# schematic_tsc.net
KiCad netlist of a schematic drawn in EAGLE
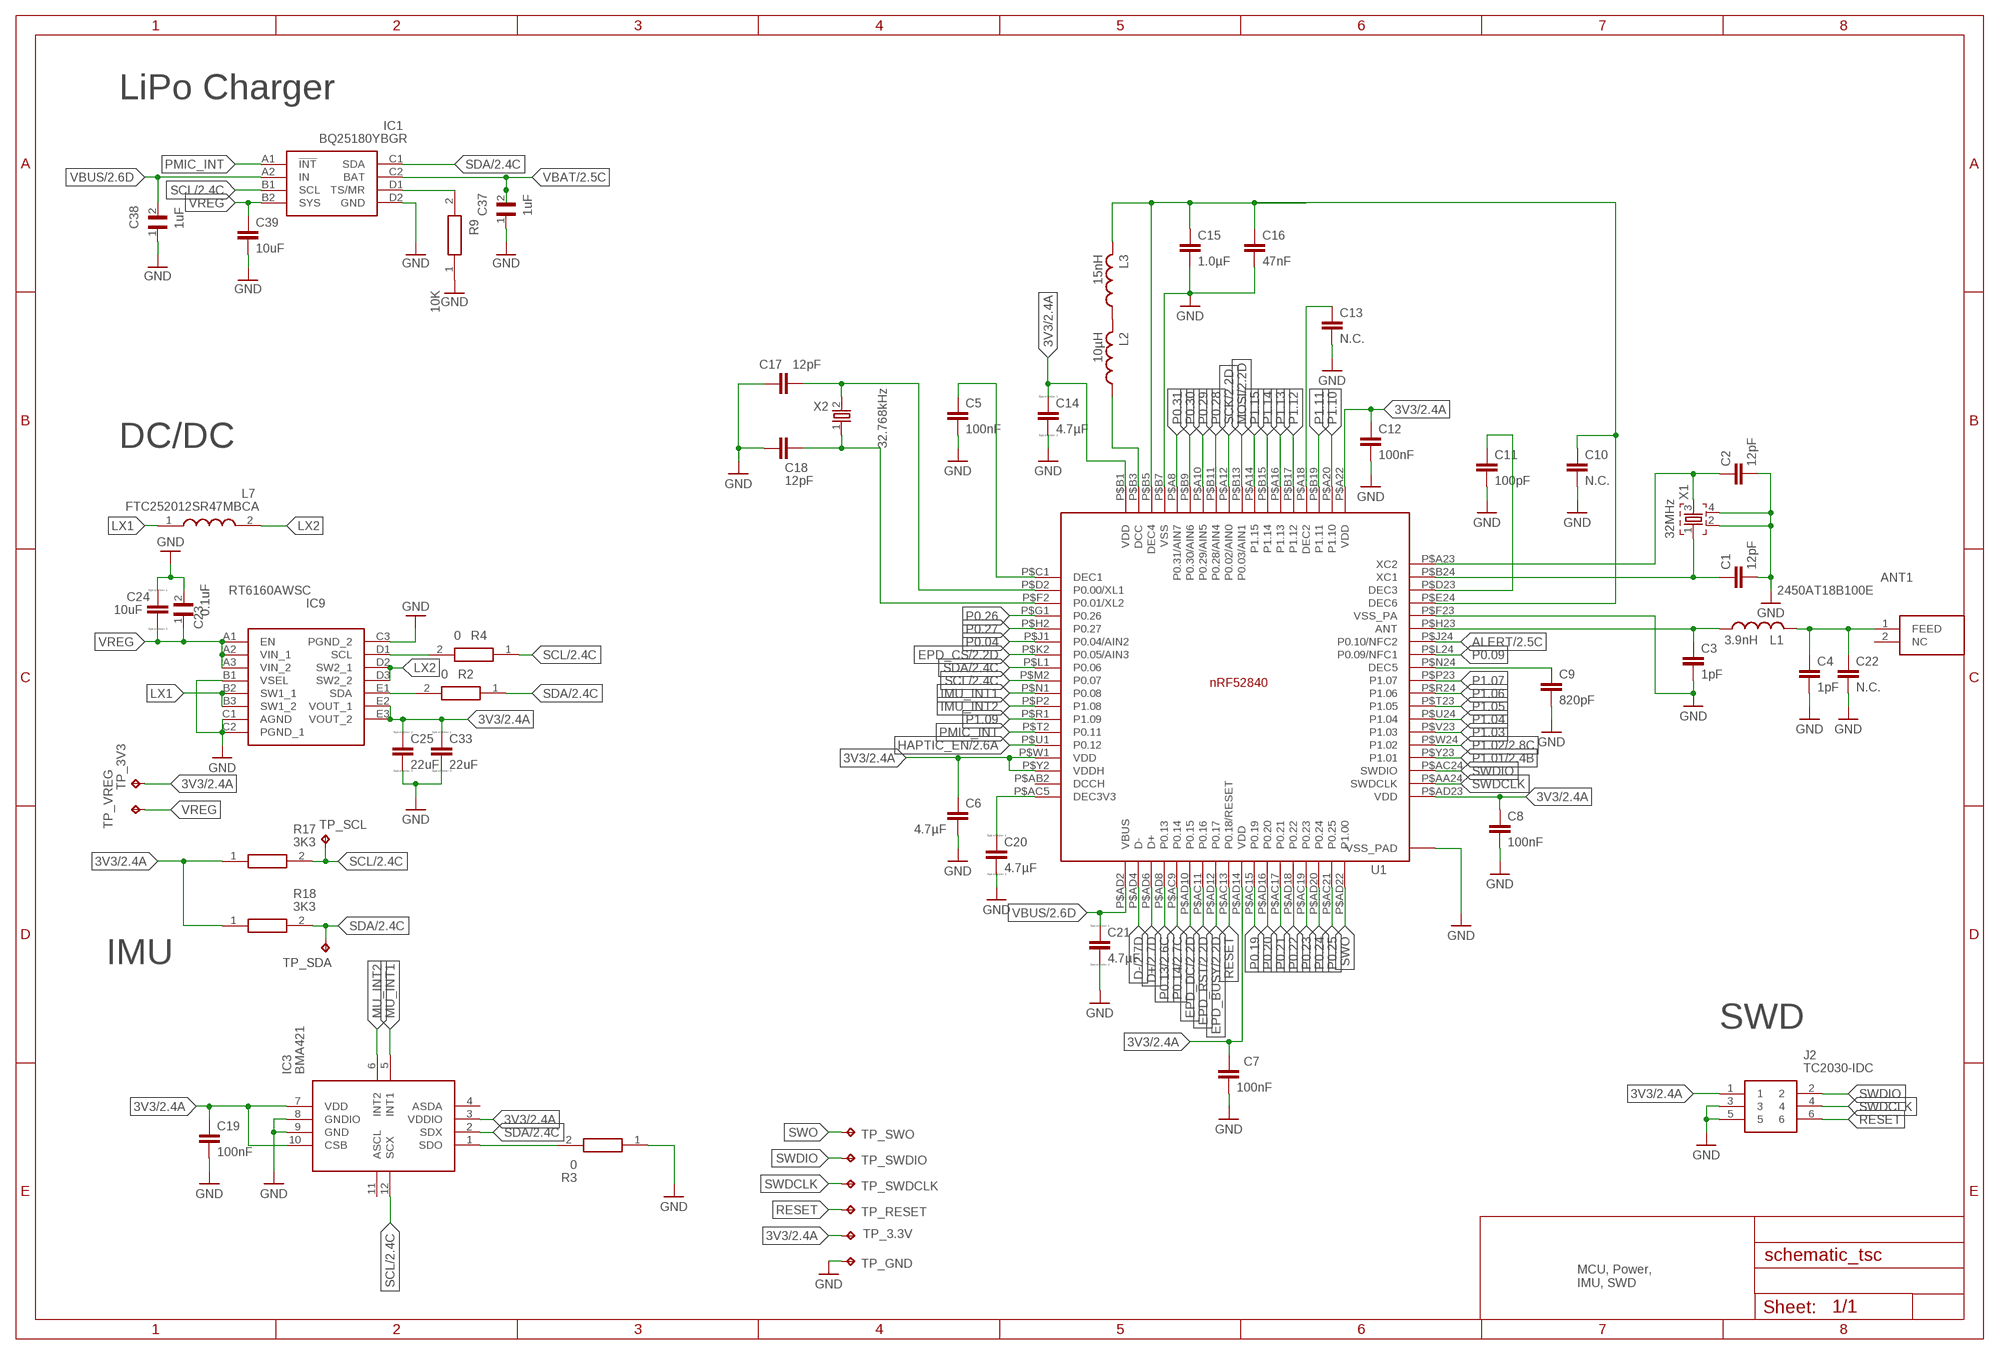
[diagram p0: schematic, sheet 1, part 1 of 2]
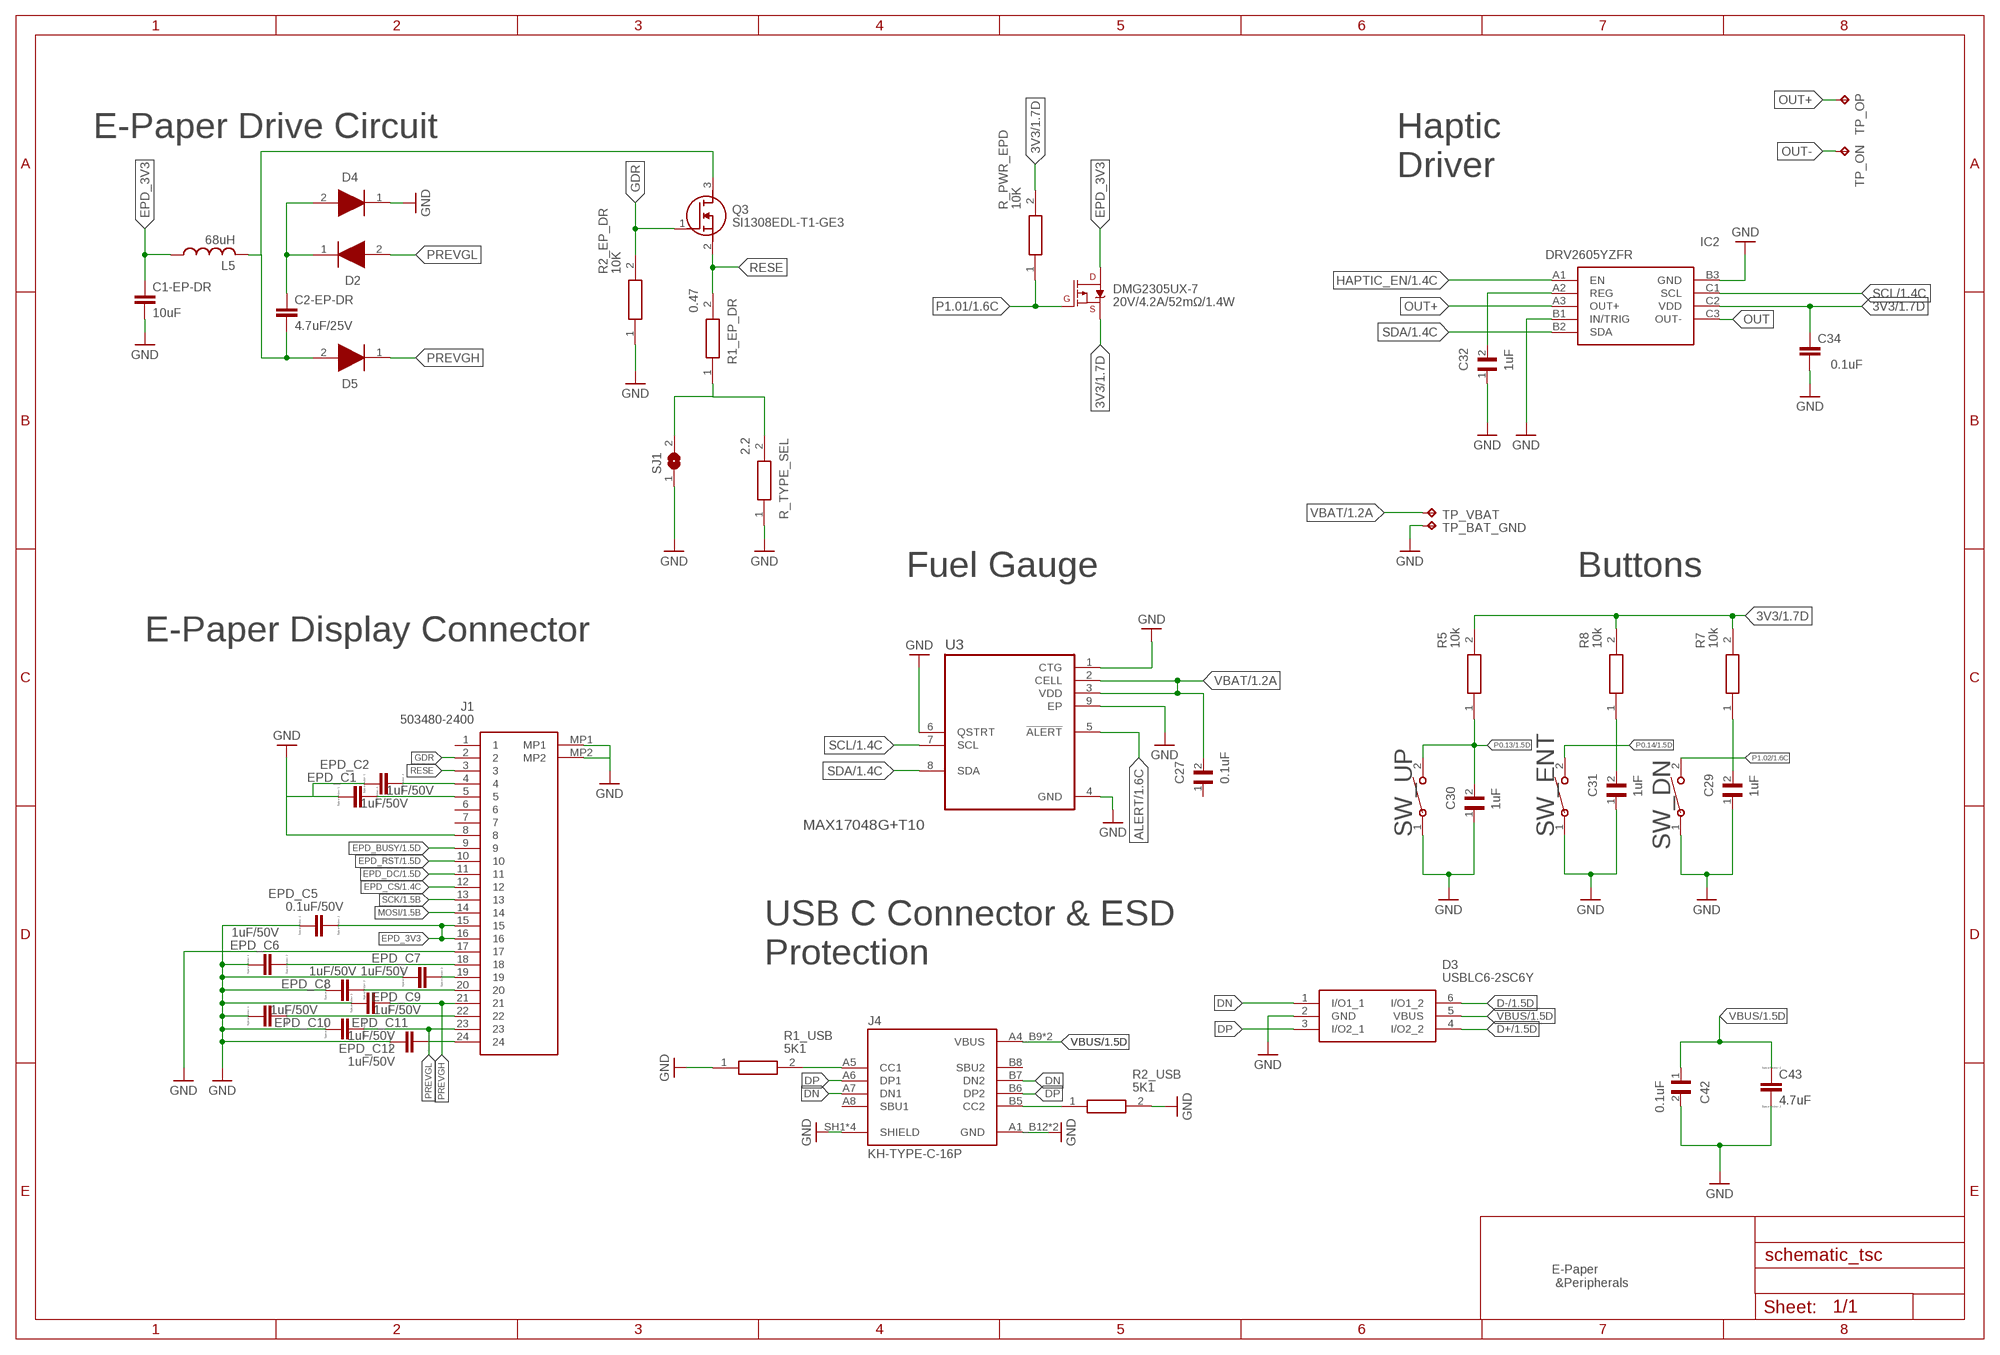
[diagram p1: schematic, sheet 1, part 2 of 2]

(export (version "E")
  (design (tool "Eeschema 10.0.6"))
  (components
    (comp (ref "ANT1")
      (value "2450AT18B100E")
      (footprint "eagle-import:2450AT18B100E_ANTC3216X140N")
      (fields (field (name "MOUSER_PART_NUMBER") "609-2450AT18B100E"))
      (libsource (lib "eagle-import") (part "2450AT18B100E_2450AT18B100E"))
    )
    (comp (ref "C1")
      (value "12pF")
      (footprint "eagle-import:NORDIC_NRF_3_RESC0201_L")
      (libsource (lib "eagle-import") (part "NORDIC_NRF_3_CAPACITOR_0201_L"))
    )
    (comp (ref "C1-EP-DR")
      (value "10uF")
      (footprint "eagle-import:NORDIC_NRF_3_RESC0201_L")
      (libsource (lib "eagle-import") (part "NORDIC_NRF_3_CAPACITOR_0201_L"))
    )
    (comp (ref "C2")
      (value "12pF")
      (footprint "eagle-import:NORDIC_NRF_3_RESC0201_L")
      (libsource (lib "eagle-import") (part "NORDIC_NRF_3_CAPACITOR_0201_L"))
    )
    (comp (ref "C2-EP-DR")
      (value "4.7uF/25V")
      (footprint "eagle-import:NORDIC_NRF_3_RESC0201_L")
      (libsource (lib "eagle-import") (part "NORDIC_NRF_3_CAPACITOR_0201_L"))
    )
    (comp (ref "C3")
      (value "1pF")
      (footprint "eagle-import:NORDIC_NRF_3_RESC0201_L")
      (libsource (lib "eagle-import") (part "NORDIC_NRF_3_CAPACITOR_0201_L"))
    )
    (comp (ref "C4")
      (value "1pF")
      (footprint "eagle-import:NORDIC_NRF_3_RESC0201_L")
      (libsource (lib "eagle-import") (part "NORDIC_NRF_3_CAPACITOR_0201_L"))
    )
    (comp (ref "C5")
      (value "100nF")
      (footprint "eagle-import:NORDIC_NRF_3_RESC0201_L")
      (libsource (lib "eagle-import") (part "NORDIC_NRF_3_CAPACITOR_0201_L"))
    )
    (comp (ref "C6")
      (value "4.7µF")
      (footprint "eagle-import:NORDIC_NRF_3_RESC0201_L")
      (libsource (lib "eagle-import") (part "NORDIC_NRF_3_CAPACITOR_0201_L"))
    )
    (comp (ref "C7")
      (value "100nF")
      (footprint "eagle-import:NORDIC_NRF_3_RESC0201_L")
      (libsource (lib "eagle-import") (part "NORDIC_NRF_3_CAPACITOR_0201_L"))
    )
    (comp (ref "C8")
      (value "100nF")
      (footprint "eagle-import:NORDIC_NRF_3_RESC0201_L")
      (libsource (lib "eagle-import") (part "NORDIC_NRF_3_CAPACITOR_0201_L"))
    )
    (comp (ref "C9")
      (value "820pF")
      (footprint "eagle-import:NORDIC_NRF_3_RESC0201_L")
      (libsource (lib "eagle-import") (part "NORDIC_NRF_3_CAPACITOR_0201_L"))
    )
    (comp (ref "C10")
      (value "N.C.")
      (footprint "eagle-import:NORDIC_NRF_3_RESC0201_L")
      (libsource (lib "eagle-import") (part "NORDIC_NRF_3_CAPACITOR_0201_L"))
    )
    (comp (ref "C11")
      (value "100pF")
      (footprint "eagle-import:NORDIC_NRF_3_RESC0201_L")
      (libsource (lib "eagle-import") (part "NORDIC_NRF_3_CAPACITOR_0201_L"))
    )
    (comp (ref "C12")
      (value "100nF")
      (footprint "eagle-import:NORDIC_NRF_3_RESC0201_L")
      (libsource (lib "eagle-import") (part "NORDIC_NRF_3_CAPACITOR_0201_L"))
    )
    (comp (ref "C13")
      (value "N.C.")
      (footprint "eagle-import:NORDIC_NRF_3_RESC0201_L")
      (libsource (lib "eagle-import") (part "NORDIC_NRF_3_CAPACITOR_0201_L"))
    )
    (comp (ref "C14")
      (value "4.7µF")
      (footprint "eagle-import:ESP32_C6_LIBRARY_1_ESP32_WROVER_EAGLE-LTSPICE_C0402")
      (libsource (lib "eagle-import") (part "ESP32_C6_LIBRARY_1_ESP32_WROVER_EAGLE-LTSPICE_CC0402"))
    )
    (comp (ref "C15")
      (value "1.0µF")
      (footprint "eagle-import:NORDIC_NRF_3_RESC0201_L")
      (libsource (lib "eagle-import") (part "NORDIC_NRF_3_CAPACITOR_0201_L"))
    )
    (comp (ref "C16")
      (value "47nF")
      (footprint "eagle-import:NORDIC_NRF_3_RESC0201_L")
      (libsource (lib "eagle-import") (part "NORDIC_NRF_3_CAPACITOR_0201_L"))
    )
    (comp (ref "C17")
      (value "12pF")
      (footprint "eagle-import:NORDIC_NRF_3_RESC0201_L")
      (libsource (lib "eagle-import") (part "NORDIC_NRF_3_CAPACITOR_0201_L"))
    )
    (comp (ref "C18")
      (value "12pF")
      (footprint "eagle-import:NORDIC_NRF_3_RESC0201_L")
      (libsource (lib "eagle-import") (part "NORDIC_NRF_3_CAPACITOR_0201_L"))
    )
    (comp (ref "C19")
      (value "100nF")
      (footprint "eagle-import:NORDIC_NRF_3_RESC0201_L")
      (libsource (lib "eagle-import") (part "NORDIC_NRF_3_CAPACITOR_0201_L"))
    )
    (comp (ref "C20")
      (value "4.7µF")
      (footprint "eagle-import:ESP32_C6_LIBRARY_1_ESP32_WROVER_EAGLE-LTSPICE_C0402")
      (libsource (lib "eagle-import") (part "ESP32_C6_LIBRARY_1_ESP32_WROVER_EAGLE-LTSPICE_CC0402"))
    )
    (comp (ref "C21")
      (value "4.7µF")
      (footprint "eagle-import:ESP32_C6_LIBRARY_1_ESP32_WROVER_EAGLE-LTSPICE_C0402")
      (libsource (lib "eagle-import") (part "ESP32_C6_LIBRARY_1_ESP32_WROVER_EAGLE-LTSPICE_CC0402"))
    )
    (comp (ref "C22")
      (value "N.C.")
      (footprint "eagle-import:NORDIC_NRF_3_RESC0201_L")
      (libsource (lib "eagle-import") (part "NORDIC_NRF_3_CAPACITOR_0201_L"))
    )
    (comp (ref "C23")
      (value "0.1uF")
      (footprint "eagle-import:GRM011R60J152KE01L_2_CAPC0201X13N")
      (fields (field (name "MF") "Murata") (field (name "MP") "GRM011R60J152KE01L"))
      (libsource (lib "eagle-import") (part "GRM011R60J152KE01L_2_GRM011R60J152KE01L"))
    )
    (comp (ref "C24")
      (value "10uF")
      (footprint "eagle-import:ESP32_C6_LIBRARY_1_ESP32_WROVER_EAGLE-LTSPICE_C0402")
      (libsource (lib "eagle-import") (part "ESP32_C6_LIBRARY_1_ESP32_WROVER_EAGLE-LTSPICE_CC0402"))
    )
    (comp (ref "C25")
      (value "22uF")
      (footprint "eagle-import:ESP32_C6_LIBRARY_1_ESP32_WROVER_EAGLE-LTSPICE_C0402")
      (libsource (lib "eagle-import") (part "ESP32_C6_LIBRARY_1_ESP32_WROVER_EAGLE-LTSPICE_CC0402"))
    )
    (comp (ref "C27")
      (value "0.1uF")
      (footprint "eagle-import:GRM011R60J152KE01L_2_CAPC0201X13N")
      (fields (field (name "MF") "Murata") (field (name "MP") "GRM011R60J152KE01L"))
      (libsource (lib "eagle-import") (part "GRM011R60J152KE01L_2_GRM011R60J152KE01L"))
    )
    (comp (ref "C29")
      (value "1uF")
      (footprint "eagle-import:GRM011R60J152KE01L_2_CAPC0201X13N")
      (fields (field (name "MF") "Murata") (field (name "MP") "GRM011R60J152KE01L"))
      (libsource (lib "eagle-import") (part "GRM011R60J152KE01L_2_GRM011R60J152KE01L"))
    )
    (comp (ref "C30")
      (value "1uF")
      (footprint "eagle-import:GRM011R60J152KE01L_2_CAPC0201X13N")
      (fields (field (name "MF") "Murata") (field (name "MP") "GRM011R60J152KE01L"))
      (libsource (lib "eagle-import") (part "GRM011R60J152KE01L_2_GRM011R60J152KE01L"))
    )
    (comp (ref "C31")
      (value "1uF")
      (footprint "eagle-import:GRM011R60J152KE01L_2_CAPC0201X13N")
      (fields (field (name "MF") "Murata") (field (name "MP") "GRM011R60J152KE01L"))
      (libsource (lib "eagle-import") (part "GRM011R60J152KE01L_2_GRM011R60J152KE01L"))
    )
    (comp (ref "C32")
      (value "1uF")
      (footprint "eagle-import:GRM011R60J152KE01L_2_CAPC0201X13N")
      (fields (field (name "MF") "Murata") (field (name "MP") "GRM011R60J152KE01L"))
      (libsource (lib "eagle-import") (part "GRM011R60J152KE01L_2_GRM011R60J152KE01L"))
    )
    (comp (ref "C33")
      (value "22uF")
      (footprint "eagle-import:ESP32_C6_LIBRARY_1_ESP32_WROVER_EAGLE-LTSPICE_C0402")
      (libsource (lib "eagle-import") (part "ESP32_C6_LIBRARY_1_ESP32_WROVER_EAGLE-LTSPICE_CC0402"))
    )
    (comp (ref "C34")
      (value "0.1uF")
      (footprint "eagle-import:NORDIC_NRF_3_RESC0201_L")
      (libsource (lib "eagle-import") (part "NORDIC_NRF_3_CAPACITOR_0201_L"))
    )
    (comp (ref "C37")
      (value "1uF")
      (footprint "eagle-import:GRM011R60J152KE01L_2_CAPC0201X13N")
      (fields (field (name "MF") "Murata") (field (name "MP") "GRM011R60J152KE01L"))
      (libsource (lib "eagle-import") (part "GRM011R60J152KE01L_2_GRM011R60J152KE01L"))
    )
    (comp (ref "C38")
      (value "1uF")
      (footprint "eagle-import:GRM011R60J152KE01L_2_CAPC0201X13N")
      (fields (field (name "MF") "Murata") (field (name "MP") "GRM011R60J152KE01L"))
      (libsource (lib "eagle-import") (part "GRM011R60J152KE01L_2_GRM011R60J152KE01L"))
    )
    (comp (ref "C39")
      (value "10uF")
      (footprint "eagle-import:NORDIC_NRF_3_RESC0201_L")
      (libsource (lib "eagle-import") (part "NORDIC_NRF_3_CAPACITOR_0201_L"))
    )
    (comp (ref "C42")
      (value "0.1uF")
      (footprint "eagle-import:GRM011R60J152KE01L_2_CAPC0201X13N")
      (fields (field (name "MF") "Murata") (field (name "MP") "GRM011R60J152KE01L"))
      (libsource (lib "eagle-import") (part "GRM011R60J152KE01L_2_GRM011R60J152KE01L"))
    )
    (comp (ref "C43")
      (value "4.7uF")
      (footprint "eagle-import:ESP32_C6_LIBRARY_1_ESP32_WROVER_EAGLE-LTSPICE_C0402")
      (libsource (lib "eagle-import") (part "ESP32_C6_LIBRARY_1_ESP32_WROVER_EAGLE-LTSPICE_CC0402"))
    )
    (comp (ref "D2")
      (value "ESP32_C6_LIBRARY_5_MBR0530")
      (footprint "eagle-import:ESP32_C6_LIBRARY_5_SOD3716X135N")
      (fields (field (name "MF") "ON Semiconductor") (field (name "MP") "MBR0530"))
      (libsource (lib "eagle-import") (part "ESP32_C6_LIBRARY_5_MBR0530"))
    )
    (comp (ref "D3")
      (value "USBLC6-2SC6Y")
      (footprint "eagle-import:ESP32_C6_LIBRARY_3_SOT95P280X145-6N")
      (fields (field (name "MF") "STMicroelectronics"))
      (libsource (lib "eagle-import") (part "ESP32_C6_LIBRARY_3_USBLC6-2SC6Y"))
    )
    (comp (ref "D4")
      (value "ESP32_C6_LIBRARY_5_MBR0530")
      (footprint "eagle-import:ESP32_C6_LIBRARY_5_SOD3716X135N")
      (fields (field (name "MF") "ON Semiconductor") (field (name "MP") "MBR0530"))
      (libsource (lib "eagle-import") (part "ESP32_C6_LIBRARY_5_MBR0530"))
    )
    (comp (ref "D5")
      (value "ESP32_C6_LIBRARY_5_MBR0530")
      (footprint "eagle-import:ESP32_C6_LIBRARY_5_SOD3716X135N")
      (fields (field (name "MF") "ON Semiconductor") (field (name "MP") "MBR0530"))
      (libsource (lib "eagle-import") (part "ESP32_C6_LIBRARY_5_MBR0530"))
    )
    (comp (ref "DMG2305UX-7")
      (value "20V/4.2A/52mΩ/1.4W")
      (footprint "eagle-import:ESP32_C6_LIBRARY_4_ESP32_C6_LIBRARY_4_ESP32_C6_LIBRARY_4_ESP32_C6_LIBRARY_4_ESP32_WROVER_SPARKFUN-DISCRETESEMI_SOT23-3")
      (libsource (lib "eagle-import") (part "ESP32_C6_LIBRARY_4_ESP32_WROVER_SPARKFUN-DISCRETESEMI_MOSFET_PCH-DMG2305UX-7"))
    )
    (comp (ref "EPD_C1")
      (value "1uF/50V")
      (footprint "eagle-import:ESP32_C6_LIBRARY_1_ESP32_WROVER_EAGLE-LTSPICE_C0402")
      (libsource (lib "eagle-import") (part "ESP32_C6_LIBRARY_1_ESP32_WROVER_EAGLE-LTSPICE_CC0402"))
    )
    (comp (ref "EPD_C2")
      (value "1uF/50V")
      (footprint "eagle-import:ESP32_C6_LIBRARY_1_ESP32_WROVER_EAGLE-LTSPICE_C0402")
      (libsource (lib "eagle-import") (part "ESP32_C6_LIBRARY_1_ESP32_WROVER_EAGLE-LTSPICE_CC0402"))
    )
    (comp (ref "EPD_C5")
      (value "0.1uF/50V")
      (footprint "eagle-import:ESP32_C6_LIBRARY_1_ESP32_WROVER_EAGLE-LTSPICE_C0402")
      (libsource (lib "eagle-import") (part "ESP32_C6_LIBRARY_1_ESP32_WROVER_EAGLE-LTSPICE_CC0402"))
    )
    (comp (ref "EPD_C6")
      (value "1uF/50V")
      (footprint "eagle-import:ESP32_C6_LIBRARY_1_ESP32_WROVER_EAGLE-LTSPICE_C0402")
      (libsource (lib "eagle-import") (part "ESP32_C6_LIBRARY_1_ESP32_WROVER_EAGLE-LTSPICE_CC0402"))
    )
    (comp (ref "EPD_C7")
      (value "1uF/50V")
      (footprint "eagle-import:ESP32_C6_LIBRARY_1_ESP32_WROVER_EAGLE-LTSPICE_C0402")
      (libsource (lib "eagle-import") (part "ESP32_C6_LIBRARY_1_ESP32_WROVER_EAGLE-LTSPICE_CC0402"))
    )
    (comp (ref "EPD_C8")
      (value "1uF/50V")
      (footprint "eagle-import:ESP32_C6_LIBRARY_1_ESP32_WROVER_EAGLE-LTSPICE_C0402")
      (libsource (lib "eagle-import") (part "ESP32_C6_LIBRARY_1_ESP32_WROVER_EAGLE-LTSPICE_CC0402"))
    )
    (comp (ref "EPD_C9")
      (value "1uF/50V")
      (footprint "eagle-import:ESP32_C6_LIBRARY_1_ESP32_WROVER_EAGLE-LTSPICE_C0402")
      (libsource (lib "eagle-import") (part "ESP32_C6_LIBRARY_1_ESP32_WROVER_EAGLE-LTSPICE_CC0402"))
    )
    (comp (ref "EPD_C10")
      (value "1uF/50V")
      (footprint "eagle-import:ESP32_C6_LIBRARY_1_ESP32_WROVER_EAGLE-LTSPICE_C0402")
      (libsource (lib "eagle-import") (part "ESP32_C6_LIBRARY_1_ESP32_WROVER_EAGLE-LTSPICE_CC0402"))
    )
    (comp (ref "EPD_C11")
      (value "1uF/50V")
      (footprint "eagle-import:ESP32_C6_LIBRARY_1_ESP32_WROVER_EAGLE-LTSPICE_C0402")
      (libsource (lib "eagle-import") (part "ESP32_C6_LIBRARY_1_ESP32_WROVER_EAGLE-LTSPICE_CC0402"))
    )
    (comp (ref "EPD_C12")
      (value "1uF/50V")
      (footprint "eagle-import:ESP32_C6_LIBRARY_1_ESP32_WROVER_EAGLE-LTSPICE_C0402")
      (libsource (lib "eagle-import") (part "ESP32_C6_LIBRARY_1_ESP32_WROVER_EAGLE-LTSPICE_CC0402"))
    )
    (comp (ref "IC1")
      (value "BQ25180YBGR")
      (footprint "eagle-import:BQ25180YBGR_BGA8C40P2X4_100X155X50")
      (fields (field (name "MOUSER_PART_NUMBER") "595-BQ25180YBGR"))
      (libsource (lib "eagle-import") (part "BQ25180YBGR_BQ25180YBGR"))
    )
    (comp (ref "IC2")
      (value "DRV2605YZFR")
      (footprint "eagle-import:DRV2605YZFR_BGA9C50P3X3_144X144X62")
      (libsource (lib "eagle-import") (part "DRV2605YZFR_DRV2605YZFR"))
    )
    (comp (ref "IC3")
      (value "BMA421")
      (footprint "eagle-import:BMA423_BMA423")
      (fields (field (name "ARROW_PART_NUMBER") "BMA423") (field (name "MOUSER_PART_NUMBER") "262-BMA423"))
      (libsource (lib "eagle-import") (part "BMA423_BMA423"))
    )
    (comp (ref "IC9")
      (value "RT6160AWSC")
      (footprint "eagle-import:RT6160AWSC_BGA15C40P3X5_140X230X60")
      (fields (field (name "MOUSER_PART_NUMBER") "835-RT6160AWSC"))
      (libsource (lib "eagle-import") (part "RT6160AWSC_RT6160AWSC"))
    )
    (comp (ref "J1")
      (value "503480-2400")
      (footprint "eagle-import:503480-2400_5034802400")
      (fields (field (name "MOUSER_PART_NUMBER") "538-503480-2400"))
      (libsource (lib "eagle-import") (part "503480-2400_503480-2400"))
    )
    (comp (ref "J2")
      (value "TC2030-IDC")
      (footprint "eagle-import:TC2030-IDC_TC2030IDC")
      (libsource (lib "eagle-import") (part "TC2030-IDC_TC2030-IDC"))
    )
    (comp (ref "J4")
      (value "KH-TYPE-C-16P")
      (footprint "eagle-import:KH-TYPE-C-16P_KINGHELM_KH-TYPE-C-16P")
      (fields (field (name "MF") "kinghelm"))
      (libsource (lib "eagle-import") (part "KH-TYPE-C-16P_KH-TYPE-C-16P"))
    )
    (comp (ref "L1")
      (value "3.9nH")
      (footprint "eagle-import:NORDIC_NRF_2_RESC0402_L")
      (libsource (lib "eagle-import") (part "NORDIC_NRF_2_INDUCTOR_0402_L"))
    )
    (comp (ref "L2")
      (value "10µH")
      (footprint "eagle-import:NORDIC_NRF_2_RESC0402_L")
      (libsource (lib "eagle-import") (part "NORDIC_NRF_2_INDUCTOR_0402_L"))
    )
    (comp (ref "L3")
      (value "15nH")
      (footprint "eagle-import:NORDIC_NRF_2_RESC0402_L")
      (libsource (lib "eagle-import") (part "NORDIC_NRF_2_INDUCTOR_0402_L"))
    )
    (comp (ref "L5")
      (value "68uH")
      (footprint "eagle-import:NORDIC_NRF_2_RESC0402_L")
      (libsource (lib "eagle-import") (part "NORDIC_NRF_2_INDUCTOR_0402_L"))
    )
    (comp (ref "L7")
      (value "FTC252012SR47MBCA")
      (footprint "eagle-import:MLP2016SR47MT0S1_INDC2016X100N")
      (libsource (lib "eagle-import") (part "MLP2016SR47MT0S1_FTC252012SR47MBCA"))
    )
    (comp (ref "Q3")
      (value "SI1308EDL-T1-GE3")
      (footprint "eagle-import:ESP32_C6_LIBRARY_6_SOT65P210X110-3N")
      (fields (field (name "MF") "Vishay Siliconix"))
      (libsource (lib "eagle-import") (part "ESP32_C6_LIBRARY_6_SI1308EDL-T1-GE3"))
    )
    (comp (ref "R1_EP_DR")
      (value "0.47")
      (footprint "eagle-import:ERA-1AEB3401C_0201")
      (libsource (lib "eagle-import") (part "ERA-1AEB3401C_CPF0201D7K68C1"))
    )
    (comp (ref "R1_USB")
      (value "5K1")
      (footprint "eagle-import:CPF0201D7K68C1_0201")
      (libsource (lib "eagle-import") (part "CPF0201D7K68C1_CPF0201D7K68C1"))
    )
    (comp (ref "R2")
      (value "0")
      (footprint "eagle-import:CPF0201D7K68C1_0201")
      (libsource (lib "eagle-import") (part "CPF0201D7K68C1_CPF0201D7K68C1"))
    )
    (comp (ref "R2_EP_DR")
      (value "10K")
      (footprint "eagle-import:ERA-1AEB3401C_0201")
      (libsource (lib "eagle-import") (part "ERA-1AEB3401C_CPF0201D7K68C1"))
    )
    (comp (ref "R2_USB")
      (value "5K1")
      (footprint "eagle-import:ERA-1AEB3401C_0201")
      (libsource (lib "eagle-import") (part "ERA-1AEB3401C_CPF0201D7K68C1"))
    )
    (comp (ref "R3")
      (value "0")
      (footprint "eagle-import:ERA-1AEB3401C_0201")
      (libsource (lib "eagle-import") (part "ERA-1AEB3401C_CPF0201D7K68C1"))
    )
    (comp (ref "R4")
      (value "0")
      (footprint "eagle-import:CPF0201D7K68C1_0201")
      (libsource (lib "eagle-import") (part "CPF0201D7K68C1_CPF0201D7K68C1"))
    )
    (comp (ref "R5")
      (value "10k")
      (footprint "eagle-import:CPF0201D7K68C1_0201")
      (libsource (lib "eagle-import") (part "CPF0201D7K68C1_CPF0201D7K68C1"))
    )
    (comp (ref "R7")
      (value "10k")
      (footprint "eagle-import:CPF0201D7K68C1_0201")
      (libsource (lib "eagle-import") (part "CPF0201D7K68C1_CPF0201D7K68C1"))
    )
    (comp (ref "R8")
      (value "10k")
      (footprint "eagle-import:CPF0201D7K68C1_0201")
      (libsource (lib "eagle-import") (part "CPF0201D7K68C1_CPF0201D7K68C1"))
    )
    (comp (ref "R9")
      (value "10K")
      (footprint "eagle-import:ERA-1AEB3401C_0201")
      (libsource (lib "eagle-import") (part "ERA-1AEB3401C_CPF0201D7K68C1"))
    )
    (comp (ref "R17")
      (value "3K3")
      (footprint "eagle-import:CPF0201D7K68C1_0201")
      (libsource (lib "eagle-import") (part "CPF0201D7K68C1_CPF0201D7K68C1"))
    )
    (comp (ref "R18")
      (value "3K3")
      (footprint "eagle-import:CPF0201D7K68C1_0201")
      (libsource (lib "eagle-import") (part "CPF0201D7K68C1_CPF0201D7K68C1"))
    )
    (comp (ref "R_PWR_EPD")
      (value "10K")
      (footprint "eagle-import:CPF0201D7K68C1_0201")
      (libsource (lib "eagle-import") (part "CPF0201D7K68C1_CPF0201D7K68C1"))
    )
    (comp (ref "R_TYPE_SEL")
      (value "2.2")
      (footprint "eagle-import:ERA-1AEB3401C_0201")
      (libsource (lib "eagle-import") (part "ERA-1AEB3401C_CPF0201D7K68C1"))
    )
    (comp (ref "SJ1")
      (value "ESP32_C6_LIBRARY_7_JUMPER_SJ")
      (footprint "eagle-import:ESP32_C6_LIBRARY_7_JUMPER_SJ")
      (libsource (lib "eagle-import") (part "ESP32_C6_LIBRARY_7_JUMPER_SJ"))
    )
    (comp (ref "SW_DN")
      (value "2025-10-22_07-23-44_LIBRARY_EVP-AKE31ASW_EVP-AKE31A_PAN")
      (footprint "eagle-import:2025-10-22_07-23-44_LIBRARY_SW_EVP-AKE31A_PAN")
      (fields
        (field (name "MANUFACTURER_PART_NUMBER") "EVP-AKE31A")
        (field (name "COPYRIGHT") "Copyright (C) 2025 Ultra Librarian. All rights reserved.")
      )
      (libsource (lib "eagle-import") (part "2025-10-22_07-23-44_LIBRARY_EVP-AKE31ASW_EVP-AKE31A_PAN"))
    )
    (comp (ref "SW_ENT")
      (value "2025-10-22_07-23-44_LIBRARY_EVP-AKE31ASW_EVP-AKE31A_PAN")
      (footprint "eagle-import:2025-10-22_07-23-44_LIBRARY_SW_EVP-AKE31A_PAN")
      (fields
        (field (name "MANUFACTURER_PART_NUMBER") "EVP-AKE31A")
        (field (name "COPYRIGHT") "Copyright (C) 2025 Ultra Librarian. All rights reserved.")
      )
      (libsource (lib "eagle-import") (part "2025-10-22_07-23-44_LIBRARY_EVP-AKE31ASW_EVP-AKE31A_PAN"))
    )
    (comp (ref "SW_UP")
      (value "2025-10-22_07-23-44_LIBRARY_EVP-AKE31ASW_EVP-AKE31A_PAN")
      (footprint "eagle-import:2025-10-22_07-23-44_LIBRARY_SW_EVP-AKE31A_PAN")
      (fields
        (field (name "MANUFACTURER_PART_NUMBER") "EVP-AKE31A")
        (field (name "COPYRIGHT") "Copyright (C) 2025 Ultra Librarian. All rights reserved.")
      )
      (libsource (lib "eagle-import") (part "2025-10-22_07-23-44_LIBRARY_EVP-AKE31ASW_EVP-AKE31A_PAN"))
    )
    (comp (ref "TP_3.3V")
      (value "HECTOR_WATCH_1_TPTP20R")
      (footprint "eagle-import:HECTOR_WATCH_1_TP20R")
      (libsource (lib "eagle-import") (part "HECTOR_WATCH_1_TPTP20R"))
    )
    (comp (ref "TP_3V3")
      (value "HECTOR_WATCH_1_TPTP20R")
      (footprint "eagle-import:HECTOR_WATCH_1_TP20R")
      (libsource (lib "eagle-import") (part "HECTOR_WATCH_1_TPTP20R"))
    )
    (comp (ref "TP_BAT_GND")
      (value "HECTOR_WATCH_1_TPTP20R")
      (footprint "eagle-import:HECTOR_WATCH_1_TP20R")
      (libsource (lib "eagle-import") (part "HECTOR_WATCH_1_TPTP20R"))
    )
    (comp (ref "TP_GND")
      (value "HECTOR_WATCH_1_TPTP20R")
      (footprint "eagle-import:HECTOR_WATCH_1_TP20R")
      (libsource (lib "eagle-import") (part "HECTOR_WATCH_1_TPTP20R"))
    )
    (comp (ref "TP_ON")
      (value "HECTOR_WATCH_1_TPTP20R")
      (footprint "eagle-import:HECTOR_WATCH_1_TP20R")
      (libsource (lib "eagle-import") (part "HECTOR_WATCH_1_TPTP20R"))
    )
    (comp (ref "TP_OP")
      (value "HECTOR_WATCH_1_TPTP20R")
      (footprint "eagle-import:HECTOR_WATCH_1_TP20R")
      (libsource (lib "eagle-import") (part "HECTOR_WATCH_1_TPTP20R"))
    )
    (comp (ref "TP_RESET")
      (value "HECTOR_WATCH_1_TPTP20R")
      (footprint "eagle-import:HECTOR_WATCH_1_TP20R")
      (libsource (lib "eagle-import") (part "HECTOR_WATCH_1_TPTP20R"))
    )
    (comp (ref "TP_SCL")
      (value "HECTOR_WATCH_1_TPTP20R")
      (footprint "eagle-import:HECTOR_WATCH_1_TP20R")
      (libsource (lib "eagle-import") (part "HECTOR_WATCH_1_TPTP20R"))
    )
    (comp (ref "TP_SDA")
      (value "HECTOR_WATCH_1_TPTP20R")
      (footprint "eagle-import:HECTOR_WATCH_1_TP20R")
      (libsource (lib "eagle-import") (part "HECTOR_WATCH_1_TPTP20R"))
    )
    (comp (ref "TP_SWDCLK")
      (value "HECTOR_WATCH_1_TPTP20R")
      (footprint "eagle-import:HECTOR_WATCH_1_TP20R")
      (libsource (lib "eagle-import") (part "HECTOR_WATCH_1_TPTP20R"))
    )
    (comp (ref "TP_SWDIO")
      (value "HECTOR_WATCH_1_TPTP20R")
      (footprint "eagle-import:HECTOR_WATCH_1_TP20R")
      (libsource (lib "eagle-import") (part "HECTOR_WATCH_1_TPTP20R"))
    )
    (comp (ref "TP_SWO")
      (value "HECTOR_WATCH_1_TPTP20R")
      (footprint "eagle-import:HECTOR_WATCH_1_TP20R")
      (libsource (lib "eagle-import") (part "HECTOR_WATCH_1_TPTP20R"))
    )
    (comp (ref "TP_VBAT")
      (value "HECTOR_WATCH_1_TPTP20R")
      (footprint "eagle-import:HECTOR_WATCH_1_TP20R")
      (libsource (lib "eagle-import") (part "HECTOR_WATCH_1_TPTP20R"))
    )
    (comp (ref "TP_VREG")
      (value "HECTOR_WATCH_1_TPTP20R")
      (footprint "eagle-import:HECTOR_WATCH_1_TP20R")
      (libsource (lib "eagle-import") (part "HECTOR_WATCH_1_TPTP20R"))
    )
    (comp (ref "U1")
      (value "NRF52840_QF")
      (footprint "eagle-import:NORDIC_NRF_4_AQFN50P700X700X85_HS-74N")
      (libsource (lib "eagle-import") (part "NORDIC_NRF_4_NRF52840_QF"))
    )
    (comp (ref "U3")
      (value "MAX17048G+T10")
      (footprint "eagle-import:ESP32_C6_LIBRARY_SON50P200X200X80-9N")
      (fields (field (name "MF") "Analog Devices"))
      (libsource (lib "eagle-import") (part "ESP32_C6_LIBRARY_MAX17048G+T10"))
    )
    (comp (ref "X1")
      (value "32MHz")
      (footprint "eagle-import:NORDIC_NRF_BT-XTAL_2016_N")
      (libsource (lib "eagle-import") (part "NORDIC_NRF_XTAL_32MHZ"))
    )
    (comp (ref "X2")
      (value "32.768kHz")
      (footprint "eagle-import:NORDIC_NRF_1_XTAL_3215_N")
      (libsource (lib "eagle-import") (part "NORDIC_NRF_1_XTAL_32KHZ"))
    )
  )
  (nets
    (net (code "1") (name "3V3{slash}1.7D") (class "Default")
      (node (ref "C34") (pin "1") (pinfunction "1_1") (pintype "passive"))
      (node (ref "DMG2305UX-7") (pin "2") (pinfunction "S_2") (pintype "bidirectional"))
      (node (ref "IC2") (pin "C2") (pinfunction "VDD_C2") (pintype "bidirectional"))
      (node (ref "R5") (pin "2") (pinfunction "2_2") (pintype "bidirectional"))
      (node (ref "R7") (pin "2") (pinfunction "2_2") (pintype "bidirectional"))
      (node (ref "R8") (pin "2") (pinfunction "2_2") (pintype "bidirectional"))
      (node (ref "R_PWR_EPD") (pin "2") (pinfunction "2_2") (pintype "bidirectional"))
    )
    (net (code "2") (name "3V3{slash}2.4A") (class "Default")
      (node (ref "C12") (pin "1") (pinfunction "1_1") (pintype "passive"))
      (node (ref "C14") (pin "1") (pinfunction "1_1") (pintype "passive"))
      (node (ref "C19") (pin "1") (pinfunction "1_1") (pintype "passive"))
      (node (ref "C25") (pin "1") (pinfunction "1_1") (pintype "passive"))
      (node (ref "C33") (pin "1") (pinfunction "1_1") (pintype "passive"))
      (node (ref "C6") (pin "1") (pinfunction "1_1") (pintype "passive"))
      (node (ref "C7") (pin "1") (pinfunction "1_1") (pintype "passive"))
      (node (ref "C8") (pin "1") (pinfunction "1_1") (pintype "passive"))
      (node (ref "IC3") (pin "10") (pinfunction "CSB_10") (pintype "bidirectional"))
      (node (ref "IC3") (pin "3") (pinfunction "VDDIO_3") (pintype "bidirectional"))
      (node (ref "IC3") (pin "7") (pinfunction "VDD_7") (pintype "bidirectional"))
      (node (ref "IC9") (pin "E2") (pinfunction "VOUT_1_E2") (pintype "bidirectional"))
      (node (ref "IC9") (pin "E3") (pinfunction "VOUT_2_E3") (pintype "bidirectional"))
      (node (ref "J2") (pin "1") (pinfunction "1_1") (pintype "bidirectional"))
      (node (ref "R17") (pin "1") (pinfunction "1_1") (pintype "bidirectional"))
      (node (ref "R18") (pin "1") (pinfunction "1_1") (pintype "bidirectional"))
      (node (ref "TP_3.3V") (pin "TP") (pinfunction "TP_TP") (pintype "input"))
      (node (ref "TP_3V3") (pin "TP") (pinfunction "TP_TP") (pintype "input"))
      (node (ref "U1") (pin "P$A22") (pinfunction "VDD_P$A22") (pintype "power_in"))
      (node (ref "U1") (pin "P$AD14") (pinfunction "VDD_P$AD14") (pintype "power_in"))
      (node (ref "U1") (pin "P$AD23") (pinfunction "VDD_P$AD23") (pintype "power_in"))
      (node (ref "U1") (pin "P$B1") (pinfunction "VDD_P$B1") (pintype "power_in"))
      (node (ref "U1") (pin "P$W1") (pinfunction "VDD_P$W1") (pintype "power_in"))
      (node (ref "U1") (pin "P$Y2") (pinfunction "VDDH_P$Y2") (pintype "power_in"))
    )
    (net (code "3") (name "ALERT{slash}1.6C") (class "Default")
      (node (ref "U3") (pin "5") (pinfunction "~{ALERT}_5") (pintype "output"))
    )
    (net (code "4") (name "ALERT{slash}2.5C") (class "Default")
      (node (ref "U1") (pin "P$J24") (pinfunction "P0.10/NFC2_P$J24") (pintype "bidirectional"))
    )
    (net (code "5") (name "D+{slash}1.5D") (class "Default")
      (node (ref "D3") (pin "4") (pinfunction "I/O2_2_4") (pintype "bidirectional"))
    )
    (net (code "6") (name "D+{slash}2.7D") (class "Default")
      (node (ref "U1") (pin "P$AD6") (pinfunction "D+_P$AD6") (pintype "bidirectional"))
    )
    (net (code "7") (name "D-{slash}1.5D") (class "Default")
      (node (ref "D3") (pin "6") (pinfunction "I/O1_2_6") (pintype "bidirectional"))
    )
    (net (code "8") (name "D-{slash}2.7D") (class "Default")
      (node (ref "U1") (pin "P$AD4") (pinfunction "D-_P$AD4") (pintype "bidirectional"))
    )
    (net (code "9") (name "DN") (class "Default")
      (node (ref "D3") (pin "1") (pinfunction "I/O1_1_1") (pintype "bidirectional"))
      (node (ref "J4") (pin "A7") (pinfunction "DN1_A7") (pintype "bidirectional"))
      (node (ref "J4") (pin "B7") (pinfunction "DN2_B7") (pintype "bidirectional"))
    )
    (net (code "10") (name "DP") (class "Default")
      (node (ref "D3") (pin "3") (pinfunction "I/O2_1_3") (pintype "bidirectional"))
      (node (ref "J4") (pin "A6") (pinfunction "DP1_A6") (pintype "bidirectional"))
      (node (ref "J4") (pin "B6") (pinfunction "DP2_B6") (pintype "bidirectional"))
    )
    (net (code "11") (name "EPD_3V3") (class "Default")
      (node (ref "C1-EP-DR") (pin "1") (pinfunction "1_1") (pintype "passive"))
      (node (ref "DMG2305UX-7") (pin "3") (pinfunction "D_3") (pintype "bidirectional"))
      (node (ref "EPD_C5") (pin "2") (pinfunction "2_2") (pintype "passive"))
      (node (ref "J1") (pin "15") (pinfunction "15_15") (pintype "bidirectional"))
      (node (ref "J1") (pin "16") (pinfunction "16_16") (pintype "bidirectional"))
      (node (ref "L5") (pin "1") (pinfunction "1_1") (pintype "passive"))
    )
    (net (code "12") (name "EPD_BUSY{slash}1.5D") (class "Default")
      (node (ref "J1") (pin "9") (pinfunction "9_9") (pintype "bidirectional"))
    )
    (net (code "13") (name "EPD_BUSY{slash}2.2D") (class "Default")
      (node (ref "U1") (pin "P$AD12") (pinfunction "P0.17_P$AD12") (pintype "bidirectional"))
    )
    (net (code "14") (name "EPD_CS{slash}1.4C") (class "Default")
      (node (ref "J1") (pin "12") (pinfunction "12_12") (pintype "bidirectional"))
    )
    (net (code "15") (name "EPD_CS{slash}2.2D") (class "Default")
      (node (ref "U1") (pin "P$K2") (pinfunction "P0.05/AIN3_P$K2") (pintype "bidirectional"))
    )
    (net (code "16") (name "EPD_DC{slash}1.5D") (class "Default")
      (node (ref "J1") (pin "11") (pinfunction "11_11") (pintype "bidirectional"))
    )
    (net (code "17") (name "EPD_DC{slash}2.2D") (class "Default")
      (node (ref "U1") (pin "P$AD10") (pinfunction "P0.15_P$AD10") (pintype "bidirectional"))
    )
    (net (code "18") (name "EPD_RST{slash}1.5D") (class "Default")
      (node (ref "J1") (pin "10") (pinfunction "10_10") (pintype "bidirectional"))
    )
    (net (code "19") (name "EPD_RST{slash}2.2D") (class "Default")
      (node (ref "U1") (pin "P$AC11") (pinfunction "P0.16_P$AC11") (pintype "bidirectional"))
    )
    (net (code "20") (name "GDR") (class "Default")
      (node (ref "J1") (pin "2") (pinfunction "2_2") (pintype "bidirectional"))
      (node (ref "Q3") (pin "1") (pinfunction "G_1") (pintype "bidirectional"))
      (node (ref "R2_EP_DR") (pin "2") (pinfunction "2_2") (pintype "bidirectional"))
    )
    (net (code "21") (name "GND") (class "Default")
      (node (ref "C1") (pin "2") (pinfunction "2_2") (pintype "passive"))
      (node (ref "C1-EP-DR") (pin "2") (pinfunction "2_2") (pintype "passive"))
      (node (ref "C10") (pin "2") (pinfunction "2_2") (pintype "passive"))
      (node (ref "C11") (pin "2") (pinfunction "2_2") (pintype "passive"))
      (node (ref "C12") (pin "2") (pinfunction "2_2") (pintype "passive"))
      (node (ref "C13") (pin "2") (pinfunction "2_2") (pintype "passive"))
      (node (ref "C14") (pin "2") (pinfunction "2_2") (pintype "passive"))
      (node (ref "C15") (pin "2") (pinfunction "2_2") (pintype "passive"))
      (node (ref "C16") (pin "2") (pinfunction "2_2") (pintype "passive"))
      (node (ref "C17") (pin "1") (pinfunction "1_1") (pintype "passive"))
      (node (ref "C18") (pin "2") (pinfunction "2_2") (pintype "passive"))
      (node (ref "C19") (pin "2") (pinfunction "2_2") (pintype "passive"))
      (node (ref "C2") (pin "2") (pinfunction "2_2") (pintype "passive"))
      (node (ref "C20") (pin "2") (pinfunction "2_2") (pintype "passive"))
      (node (ref "C21") (pin "2") (pinfunction "2_2") (pintype "passive"))
      (node (ref "C22") (pin "2") (pinfunction "2_2") (pintype "passive"))
      (node (ref "C23") (pin "2") (pinfunction "2_2") (pintype "passive"))
      (node (ref "C24") (pin "1") (pinfunction "1_1") (pintype "passive"))
      (node (ref "C25") (pin "2") (pinfunction "2_2") (pintype "passive"))
      (node (ref "C29") (pin "1") (pinfunction "1_1") (pintype "passive"))
      (node (ref "C3") (pin "2") (pinfunction "2_2") (pintype "passive"))
      (node (ref "C30") (pin "1") (pinfunction "1_1") (pintype "passive"))
      (node (ref "C31") (pin "1") (pinfunction "1_1") (pintype "passive"))
      (node (ref "C32") (pin "1") (pinfunction "1_1") (pintype "passive"))
      (node (ref "C33") (pin "2") (pinfunction "2_2") (pintype "passive"))
      (node (ref "C34") (pin "2") (pinfunction "2_2") (pintype "passive"))
      (node (ref "C37") (pin "1") (pinfunction "1_1") (pintype "passive"))
      (node (ref "C38") (pin "1") (pinfunction "1_1") (pintype "passive"))
      (node (ref "C39") (pin "2") (pinfunction "2_2") (pintype "passive"))
      (node (ref "C4") (pin "2") (pinfunction "2_2") (pintype "passive"))
      (node (ref "C42") (pin "2") (pinfunction "2_2") (pintype "passive"))
      (node (ref "C43") (pin "2") (pinfunction "2_2") (pintype "passive"))
      (node (ref "C5") (pin "2") (pinfunction "2_2") (pintype "passive"))
      (node (ref "C6") (pin "2") (pinfunction "2_2") (pintype "passive"))
      (node (ref "C7") (pin "2") (pinfunction "2_2") (pintype "passive"))
      (node (ref "C8") (pin "2") (pinfunction "2_2") (pintype "passive"))
      (node (ref "C9") (pin "2") (pinfunction "2_2") (pintype "passive"))
      (node (ref "D3") (pin "2") (pinfunction "GND_2") (pintype "bidirectional"))
      (node (ref "D4") (pin "1") (pinfunction "K_1") (pintype "bidirectional"))
      (node (ref "EPD_C10") (pin "1") (pinfunction "1_1") (pintype "passive"))
      (node (ref "EPD_C11") (pin "1") (pinfunction "1_1") (pintype "passive"))
      (node (ref "EPD_C12") (pin "1") (pinfunction "1_1") (pintype "passive"))
      (node (ref "EPD_C5") (pin "1") (pinfunction "1_1") (pintype "passive"))
      (node (ref "EPD_C6") (pin "1") (pinfunction "1_1") (pintype "passive"))
      (node (ref "EPD_C7") (pin "1") (pinfunction "1_1") (pintype "passive"))
      (node (ref "EPD_C8") (pin "1") (pinfunction "1_1") (pintype "passive"))
      (node (ref "EPD_C9") (pin "1") (pinfunction "1_1") (pintype "passive"))
      (node (ref "IC1") (pin "D2") (pinfunction "GND_D2") (pintype "bidirectional"))
      (node (ref "IC2") (pin "B1") (pinfunction "IN/TRIG_B1") (pintype "bidirectional"))
      (node (ref "IC2") (pin "B3") (pinfunction "GND_B3") (pintype "bidirectional"))
      (node (ref "IC3") (pin "8") (pinfunction "GNDIO_8") (pintype "bidirectional"))
      (node (ref "IC3") (pin "9") (pinfunction "GND_9") (pintype "bidirectional"))
      (node (ref "IC9") (pin "B1") (pinfunction "VSEL_B1") (pintype "bidirectional"))
      (node (ref "IC9") (pin "C1") (pinfunction "AGND_C1") (pintype "bidirectional"))
      (node (ref "IC9") (pin "C2") (pinfunction "PGND_1_C2") (pintype "bidirectional"))
      (node (ref "IC9") (pin "C3") (pinfunction "PGND_2_C3") (pintype "bidirectional"))
      (node (ref "J1") (pin "17") (pinfunction "17_17") (pintype "bidirectional"))
      (node (ref "J1") (pin "8") (pinfunction "8_8") (pintype "bidirectional"))
      (node (ref "J1") (pin "MP1") (pinfunction "MP1_MP1") (pintype "bidirectional"))
      (node (ref "J2") (pin "3") (pinfunction "3_3") (pintype "bidirectional"))
      (node (ref "J2") (pin "5") (pinfunction "5_5") (pintype "bidirectional"))
      (node (ref "J4") (pin "A12_B1") (pinfunction "GND_A12_B1") (pintype "power_in"))
      (node (ref "J4") (pin "A1_B12") (pinfunction "GND_A1_B12") (pintype "power_in"))
      (node (ref "J4") (pin "SH1") (pinfunction "SHIELD_SH1") (pintype "passive"))
      (node (ref "J4") (pin "SH2") (pinfunction "SHIELD_SH2") (pintype "passive"))
      (node (ref "J4") (pin "SH3") (pinfunction "SHIELD_SH3") (pintype "passive"))
      (node (ref "J4") (pin "SH4") (pinfunction "SHIELD_SH4") (pintype "passive"))
      (node (ref "R1_USB") (pin "1") (pinfunction "1_1") (pintype "bidirectional"))
      (node (ref "R2_EP_DR") (pin "1") (pinfunction "1_1") (pintype "bidirectional"))
      (node (ref "R2_USB") (pin "2") (pinfunction "2_2") (pintype "bidirectional"))
      (node (ref "R3") (pin "1") (pinfunction "1_1") (pintype "bidirectional"))
      (node (ref "R9") (pin "1") (pinfunction "1_1") (pintype "bidirectional"))
      (node (ref "R_TYPE_SEL") (pin "1") (pinfunction "1_1") (pintype "bidirectional"))
      (node (ref "SJ1") (pin "1") (pinfunction "1_1") (pintype "passive"))
      (node (ref "SW_DN") (pin "1") (pinfunction "1_1") (pintype "passive"))
      (node (ref "SW_ENT") (pin "1") (pinfunction "1_1") (pintype "passive"))
      (node (ref "SW_UP") (pin "1") (pinfunction "1_1") (pintype "passive"))
      (node (ref "TP_BAT_GND") (pin "TP") (pinfunction "TP_TP") (pintype "input"))
      (node (ref "TP_GND") (pin "TP") (pinfunction "TP_TP") (pintype "input"))
      (node (ref "U1") (pin "P$74") (pinfunction "VSS_PAD_P$74") (pintype "bidirectional"))
      (node (ref "U1") (pin "P$75") (pinfunction "VSS_PAD_P$75") (pintype "bidirectional"))
      (node (ref "U1") (pin "P$76") (pinfunction "VSS_PAD_P$76") (pintype "bidirectional"))
      (node (ref "U1") (pin "P$77") (pinfunction "VSS_PAD_P$77") (pintype "bidirectional"))
      (node (ref "U1") (pin "P$78") (pinfunction "VSS_PAD_P$78") (pintype "bidirectional"))
      (node (ref "U1") (pin "P$79") (pinfunction "VSS_PAD_P$79") (pintype "bidirectional"))
      (node (ref "U1") (pin "P$80") (pinfunction "VSS_PAD_P$80") (pintype "bidirectional"))
      (node (ref "U1") (pin "P$81") (pinfunction "VSS_PAD_P$81") (pintype "bidirectional"))
      (node (ref "U1") (pin "P$82") (pinfunction "VSS_PAD_P$82") (pintype "bidirectional"))
      (node (ref "U1") (pin "P$83") (pinfunction "VSS_PAD_P$83") (pintype "bidirectional"))
      (node (ref "U1") (pin "P$84") (pinfunction "VSS_PAD_P$84") (pintype "bidirectional"))
      (node (ref "U1") (pin "P$85") (pinfunction "VSS_PAD_P$85") (pintype "bidirectional"))
      (node (ref "U1") (pin "P$86") (pinfunction "VSS_PAD_P$86") (pintype "bidirectional"))
      (node (ref "U1") (pin "P$87") (pinfunction "VSS_PAD_P$87") (pintype "bidirectional"))
      (node (ref "U1") (pin "P$88") (pinfunction "VSS_PAD_P$88") (pintype "bidirectional"))
      (node (ref "U1") (pin "P$89") (pinfunction "VSS_PAD_P$89") (pintype "bidirectional"))
      (node (ref "U1") (pin "P$90") (pinfunction "VSS_PAD_P$90") (pintype "bidirectional"))
      (node (ref "U1") (pin "P$B7") (pinfunction "VSS_P$B7") (pintype "power_in"))
      (node (ref "U1") (pin "P$F23") (pinfunction "VSS_PA_P$F23") (pintype "bidirectional"))
      (node (ref "U3") (pin "1") (pinfunction "CTG_1") (pintype "power_in"))
      (node (ref "U3") (pin "4") (pinfunction "GND_4") (pintype "power_in"))
      (node (ref "U3") (pin "6") (pinfunction "QSTRT_6") (pintype "input"))
      (node (ref "U3") (pin "9") (pinfunction "EP_9") (pintype "power_in"))
      (node (ref "X1") (pin "2") (pinfunction "2_2") (pintype "passive"))
      (node (ref "X1") (pin "4") (pinfunction "4_4") (pintype "passive"))
    )
    (net (code "22") (name "HAPTIC_EN{slash}1.4C") (class "Default")
      (node (ref "IC2") (pin "A1") (pinfunction "EN_A1") (pintype "bidirectional"))
    )
    (net (code "23") (name "HAPTIC_EN{slash}2.6A") (class "Default")
      (node (ref "U1") (pin "P$U1") (pinfunction "P0.12_P$U1") (pintype "bidirectional"))
    )
    (net (code "24") (name "IMU_INT1") (class "Default")
      (node (ref "U1") (pin "P$N1") (pinfunction "P0.08_P$N1") (pintype "bidirectional"))
    )
    (net (code "25") (name "IMU_INT2") (class "Default")
      (node (ref "U1") (pin "P$P2") (pinfunction "P1.08_P$P2") (pintype "bidirectional"))
    )
    (net (code "26") (name "LX1") (class "Default")
      (node (ref "IC9") (pin "B2") (pinfunction "SW1_1_B2") (pintype "bidirectional"))
      (node (ref "IC9") (pin "B3") (pinfunction "SW1_2_B3") (pintype "bidirectional"))
      (node (ref "L7") (pin "1") (pinfunction "1_1") (pintype "bidirectional"))
    )
    (net (code "27") (name "LX2") (class "Default")
      (node (ref "IC9") (pin "D2") (pinfunction "SW2_1_D2") (pintype "bidirectional"))
      (node (ref "IC9") (pin "D3") (pinfunction "SW2_2_D3") (pintype "bidirectional"))
      (node (ref "L7") (pin "2") (pinfunction "2_2") (pintype "bidirectional"))
    )
    (net (code "28") (name "MOSI{slash}1.5B") (class "Default")
      (node (ref "J1") (pin "14") (pinfunction "14_14") (pintype "bidirectional"))
    )
    (net (code "29") (name "MOSI{slash}2.2D") (class "Default")
      (node (ref "U1") (pin "P$B13") (pinfunction "P0.03/AIN1_P$B13") (pintype "bidirectional"))
    )
    (net (code "30") (name "MU_INT1") (class "Default")
      (node (ref "IC3") (pin "5") (pinfunction "INT1_5") (pintype "bidirectional"))
    )
    (net (code "31") (name "MU_INT2") (class "Default")
      (node (ref "IC3") (pin "6") (pinfunction "INT2_6") (pintype "bidirectional"))
    )
    (net (code "32") (name "Net-(ANT1-FEED)") (class "Default")
      (node (ref "ANT1") (pin "1") (pinfunction "FEED_1") (pintype "input"))
      (node (ref "C22") (pin "1") (pinfunction "1_1") (pintype "passive"))
      (node (ref "C4") (pin "1") (pinfunction "1_1") (pintype "passive"))
      (node (ref "L1") (pin "2") (pinfunction "2_2") (pintype "passive"))
    )
    (net (code "33") (name "Net-(C29-Pad2)") (class "Default")
      (node (ref "C29") (pin "2") (pinfunction "2_2") (pintype "passive"))
      (node (ref "R7") (pin "1") (pinfunction "1_1") (pintype "bidirectional"))
    )
    (net (code "34") (name "Net-(C31-Pad2)") (class "Default")
      (node (ref "C31") (pin "2") (pinfunction "2_2") (pintype "passive"))
      (node (ref "R8") (pin "1") (pinfunction "1_1") (pintype "bidirectional"))
    )
    (net (code "35") (name "Net-(D2-K)") (class "Default")
      (node (ref "C2-EP-DR") (pin "1") (pinfunction "1_1") (pintype "passive"))
      (node (ref "D2") (pin "1") (pinfunction "K_1") (pintype "bidirectional"))
      (node (ref "D4") (pin "2") (pinfunction "A_2") (pintype "bidirectional"))
    )
    (net (code "36") (name "Net-(D5-A)") (class "Default")
      (node (ref "C2-EP-DR") (pin "2") (pinfunction "2_2") (pintype "passive"))
      (node (ref "D5") (pin "2") (pinfunction "A_2") (pintype "bidirectional"))
      (node (ref "L5") (pin "2") (pinfunction "2_2") (pintype "passive"))
      (node (ref "Q3") (pin "3") (pinfunction "D_3") (pintype "bidirectional"))
    )
    (net (code "37") (name "Net-(EPD_C1-Pad2)") (class "Default")
      (node (ref "EPD_C1") (pin "2") (pinfunction "2_2") (pintype "passive"))
      (node (ref "J1") (pin "5") (pinfunction "5_5") (pintype "bidirectional"))
    )
    (net (code "38") (name "Net-(EPD_C2-Pad2)") (class "Default")
      (node (ref "EPD_C2") (pin "2") (pinfunction "2_2") (pintype "passive"))
      (node (ref "J1") (pin "4") (pinfunction "4_4") (pintype "bidirectional"))
    )
    (net (code "39") (name "Net-(EPD_C6-Pad2)") (class "Default")
      (node (ref "EPD_C6") (pin "2") (pinfunction "2_2") (pintype "passive"))
      (node (ref "J1") (pin "18") (pinfunction "18_18") (pintype "bidirectional"))
    )
    (net (code "40") (name "Net-(EPD_C7-Pad2)") (class "Default")
      (node (ref "EPD_C7") (pin "2") (pinfunction "2_2") (pintype "passive"))
      (node (ref "J1") (pin "19") (pinfunction "19_19") (pintype "bidirectional"))
    )
    (net (code "41") (name "Net-(EPD_C8-Pad2)") (class "Default")
      (node (ref "EPD_C8") (pin "2") (pinfunction "2_2") (pintype "passive"))
      (node (ref "J1") (pin "20") (pinfunction "20_20") (pintype "bidirectional"))
    )
    (net (code "42") (name "Net-(EPD_C10-Pad2)") (class "Default")
      (node (ref "EPD_C10") (pin "2") (pinfunction "2_2") (pintype "passive"))
      (node (ref "J1") (pin "22") (pinfunction "22_22") (pintype "bidirectional"))
    )
    (net (code "43") (name "Net-(EPD_C12-Pad2)") (class "Default")
      (node (ref "EPD_C12") (pin "2") (pinfunction "2_2") (pintype "passive"))
      (node (ref "J1") (pin "24") (pinfunction "24_24") (pintype "bidirectional"))
    )
    (net (code "44") (name "Net-(IC1-TS{slash}MR)") (class "Default")
      (node (ref "IC1") (pin "D1") (pinfunction "TS/MR_D1") (pintype "bidirectional"))
      (node (ref "R9") (pin "2") (pinfunction "2_2") (pintype "bidirectional"))
    )
    (net (code "45") (name "Net-(IC2-REG)") (class "Default")
      (node (ref "C32") (pin "2") (pinfunction "2_2") (pintype "passive"))
      (node (ref "IC2") (pin "A2") (pinfunction "REG_A2") (pintype "bidirectional"))
    )
    (net (code "46") (name "Net-(IC3-SDO)") (class "Default")
      (node (ref "IC3") (pin "1") (pinfunction "SDO_1") (pintype "bidirectional"))
      (node (ref "R3") (pin "2") (pinfunction "2_2") (pintype "bidirectional"))
    )
    (net (code "47") (name "Net-(IC9-SCL)") (class "Default")
      (node (ref "IC9") (pin "D1") (pinfunction "SCL_D1") (pintype "bidirectional"))
      (node (ref "R4") (pin "2") (pinfunction "2_2") (pintype "bidirectional"))
    )
    (net (code "48") (name "Net-(IC9-SDA)") (class "Default")
      (node (ref "IC9") (pin "E1") (pinfunction "SDA_E1") (pintype "bidirectional"))
      (node (ref "R2") (pin "2") (pinfunction "2_2") (pintype "bidirectional"))
    )
    (net (code "49") (name "Net-(J4-CC1)") (class "Default")
      (node (ref "J4") (pin "A5") (pinfunction "CC1_A5") (pintype "bidirectional"))
      (node (ref "R1_USB") (pin "2") (pinfunction "2_2") (pintype "bidirectional"))
    )
    (net (code "50") (name "Net-(J4-CC2)") (class "Default")
      (node (ref "J4") (pin "B5") (pinfunction "CC2_B5") (pintype "bidirectional"))
      (node (ref "R2_USB") (pin "1") (pinfunction "1_1") (pintype "bidirectional"))
    )
    (net (code "51") (name "Net-(L2-Pad2)") (class "Default")
      (node (ref "L2") (pin "2") (pinfunction "2_2") (pintype "passive"))
      (node (ref "L3") (pin "1") (pinfunction "1_1") (pintype "passive"))
    )
    (net (code "52") (name "Net-(R1_EP_DR-Pad1)") (class "Default")
      (node (ref "R1_EP_DR") (pin "1") (pinfunction "1_1") (pintype "bidirectional"))
      (node (ref "R_TYPE_SEL") (pin "2") (pinfunction "2_2") (pintype "bidirectional"))
      (node (ref "SJ1") (pin "2") (pinfunction "2_2") (pintype "passive"))
    )
    (net (code "53") (name "Net-(U1-ANT)") (class "Default")
      (node (ref "C3") (pin "1") (pinfunction "1_1") (pintype "passive"))
      (node (ref "L1") (pin "1") (pinfunction "1_1") (pintype "passive"))
      (node (ref "U1") (pin "P$H23") (pinfunction "ANT_P$H23") (pintype "bidirectional"))
    )
    (net (code "54") (name "Net-(U1-DCC)") (class "Default")
      (node (ref "L2") (pin "1") (pinfunction "1_1") (pintype "passive"))
      (node (ref "U1") (pin "P$B3") (pinfunction "DCC_P$B3") (pintype "output"))
    )
    (net (code "55") (name "Net-(U1-DEC1)") (class "Default")
      (node (ref "C5") (pin "1") (pinfunction "1_1") (pintype "passive"))
      (node (ref "U1") (pin "P$C1") (pinfunction "DEC1_P$C1") (pintype "power_in"))
    )
    (net (code "56") (name "Net-(U1-DEC2)") (class "Default")
      (node (ref "C13") (pin "1") (pinfunction "1_1") (pintype "passive"))
      (node (ref "U1") (pin "P$A18") (pinfunction "DEC2_P$A18") (pintype "bidirectional"))
    )
    (net (code "57") (name "Net-(U1-DEC3)") (class "Default")
      (node (ref "C11") (pin "1") (pinfunction "1_1") (pintype "passive"))
      (node (ref "U1") (pin "P$D23") (pinfunction "DEC3_P$D23") (pintype "bidirectional"))
    )
    (net (code "58") (name "Net-(U1-DEC3V3)") (class "Default")
      (node (ref "C20") (pin "1") (pinfunction "1_1") (pintype "passive"))
      (node (ref "U1") (pin "P$AC5") (pinfunction "DEC3V3_P$AC5") (pintype "bidirectional"))
    )
    (net (code "59") (name "Net-(U1-DEC4)") (class "Default")
      (node (ref "C10") (pin "1") (pinfunction "1_1") (pintype "passive"))
      (node (ref "C15") (pin "1") (pinfunction "1_1") (pintype "passive"))
      (node (ref "C16") (pin "1") (pinfunction "1_1") (pintype "passive"))
      (node (ref "L3") (pin "2") (pinfunction "2_2") (pintype "passive"))
      (node (ref "U1") (pin "P$B5") (pinfunction "DEC4_P$B5") (pintype "power_in"))
      (node (ref "U1") (pin "P$E24") (pinfunction "DEC6_P$E24") (pintype "bidirectional"))
    )
    (net (code "60") (name "Net-(U1-DEC5)") (class "Default")
      (node (ref "C9") (pin "1") (pinfunction "1_1") (pintype "passive"))
      (node (ref "U1") (pin "P$N24") (pinfunction "DEC5_P$N24") (pintype "bidirectional"))
    )
    (net (code "61") (name "Net-(U1-P0.00{slash}XL1)") (class "Default")
      (node (ref "C17") (pin "2") (pinfunction "2_2") (pintype "passive"))
      (node (ref "U1") (pin "P$D2") (pinfunction "P0.00/XL1_P$D2") (pintype "bidirectional"))
      (node (ref "X2") (pin "2") (pinfunction "2_2") (pintype "passive"))
    )
    (net (code "62") (name "Net-(U1-P0.01{slash}XL2)") (class "Default")
      (node (ref "C18") (pin "1") (pinfunction "1_1") (pintype "passive"))
      (node (ref "U1") (pin "P$F2") (pinfunction "P0.01/XL2_P$F2") (pintype "bidirectional"))
      (node (ref "X2") (pin "1") (pinfunction "1_1") (pintype "passive"))
    )
    (net (code "63") (name "Net-(U1-XC1)") (class "Default")
      (node (ref "C1") (pin "1") (pinfunction "1_1") (pintype "passive"))
      (node (ref "U1") (pin "P$B24") (pinfunction "XC1_P$B24") (pintype "input"))
      (node (ref "X1") (pin "1") (pinfunction "1_1") (pintype "passive"))
    )
    (net (code "64") (name "Net-(U1-XC2)") (class "Default")
      (node (ref "C2") (pin "1") (pinfunction "1_1") (pintype "passive"))
      (node (ref "U1") (pin "P$A23") (pinfunction "XC2_P$A23") (pintype "output"))
      (node (ref "X1") (pin "3") (pinfunction "3_3") (pintype "passive"))
    )
    (net (code "65") (name "OUT") (class "Default")
      (node (ref "IC2") (pin "C3") (pinfunction "OUT-_C3") (pintype "bidirectional"))
    )
    (net (code "66") (name "OUT+") (class "Default")
      (node (ref "IC2") (pin "A3") (pinfunction "OUT+_A3") (pintype "bidirectional"))
      (node (ref "TP_OP") (pin "TP") (pinfunction "TP_TP") (pintype "input"))
    )
    (net (code "67") (name "OUT-") (class "Default")
      (node (ref "TP_ON") (pin "TP") (pinfunction "TP_TP") (pintype "input"))
    )
    (net (code "68") (name "P0.04") (class "Default")
      (node (ref "U1") (pin "P$J1") (pinfunction "P0.04/AIN2_P$J1") (pintype "bidirectional"))
    )
    (net (code "69") (name "P0.09") (class "Default")
      (node (ref "U1") (pin "P$L24") (pinfunction "P0.09/NFC1_P$L24") (pintype "bidirectional"))
    )
    (net (code "70") (name "P0.13{slash}1.5D") (class "Default")
      (node (ref "C30") (pin "2") (pinfunction "2_2") (pintype "passive"))
      (node (ref "R5") (pin "1") (pinfunction "1_1") (pintype "bidirectional"))
      (node (ref "SW_UP") (pin "2") (pinfunction "2_2") (pintype "passive"))
    )
    (net (code "71") (name "P0.13{slash}2.6C") (class "Default")
      (node (ref "U1") (pin "P$AD8") (pinfunction "P0.13_P$AD8") (pintype "bidirectional"))
    )
    (net (code "72") (name "P0.14{slash}1.5D") (class "Default")
      (node (ref "SW_ENT") (pin "2") (pinfunction "2_2") (pintype "passive"))
    )
    (net (code "73") (name "P0.14{slash}2.7C") (class "Default")
      (node (ref "U1") (pin "P$AC9") (pinfunction "P0.14_P$AC9") (pintype "bidirectional"))
    )
    (net (code "74") (name "P0.19") (class "Default")
      (node (ref "U1") (pin "P$AC15") (pinfunction "P0.19_P$AC15") (pintype "bidirectional"))
    )
    (net (code "75") (name "P0.20") (class "Default")
      (node (ref "U1") (pin "P$AD16") (pinfunction "P0.20_P$AD16") (pintype "bidirectional"))
    )
    (net (code "76") (name "P0.21") (class "Default")
      (node (ref "U1") (pin "P$AC17") (pinfunction "P0.21_P$AC17") (pintype "bidirectional"))
    )
    (net (code "77") (name "P0.22") (class "Default")
      (node (ref "U1") (pin "P$AD18") (pinfunction "P0.22_P$AD18") (pintype "bidirectional"))
    )
    (net (code "78") (name "P0.23") (class "Default")
      (node (ref "U1") (pin "P$AC19") (pinfunction "P0.23_P$AC19") (pintype "bidirectional"))
    )
    (net (code "79") (name "P0.24") (class "Default")
      (node (ref "U1") (pin "P$AD20") (pinfunction "P0.24_P$AD20") (pintype "bidirectional"))
    )
    (net (code "80") (name "P0.25") (class "Default")
      (node (ref "U1") (pin "P$AC21") (pinfunction "P0.25_P$AC21") (pintype "bidirectional"))
    )
    (net (code "81") (name "P0.26") (class "Default")
      (node (ref "U1") (pin "P$G1") (pinfunction "P0.26_P$G1") (pintype "bidirectional"))
    )
    (net (code "82") (name "P0.27") (class "Default")
      (node (ref "U1") (pin "P$H2") (pinfunction "P0.27_P$H2") (pintype "bidirectional"))
    )
    (net (code "83") (name "P0.28") (class "Default")
      (node (ref "U1") (pin "P$B11") (pinfunction "P0.28/AIN4_P$B11") (pintype "bidirectional"))
    )
    (net (code "84") (name "P0.29") (class "Default")
      (node (ref "U1") (pin "P$A10") (pinfunction "P0.29/AIN5_P$A10") (pintype "bidirectional"))
    )
    (net (code "85") (name "P0.30") (class "Default")
      (node (ref "U1") (pin "P$B9") (pinfunction "P0.30/AIN6_P$B9") (pintype "bidirectional"))
    )
    (net (code "86") (name "P0.31") (class "Default")
      (node (ref "U1") (pin "P$A8") (pinfunction "P0.31/AIN7_P$A8") (pintype "bidirectional"))
    )
    (net (code "87") (name "P1.01{slash}1.6C") (class "Default")
      (node (ref "DMG2305UX-7") (pin "1") (pinfunction "G_1") (pintype "bidirectional"))
      (node (ref "R_PWR_EPD") (pin "1") (pinfunction "1_1") (pintype "bidirectional"))
    )
    (net (code "88") (name "P1.01{slash}2.4B") (class "Default")
      (node (ref "U1") (pin "P$Y23") (pinfunction "P1.01_P$Y23") (pintype "bidirectional"))
    )
    (net (code "89") (name "P1.02{slash}1.6C") (class "Default")
      (node (ref "SW_DN") (pin "2") (pinfunction "2_2") (pintype "passive"))
    )
    (net (code "90") (name "P1.02{slash}2.8C") (class "Default")
      (node (ref "U1") (pin "P$W24") (pinfunction "P1.02_P$W24") (pintype "bidirectional"))
    )
    (net (code "91") (name "P1.03") (class "Default")
      (node (ref "U1") (pin "P$V23") (pinfunction "P1.03_P$V23") (pintype "bidirectional"))
    )
    (net (code "92") (name "P1.04") (class "Default")
      (node (ref "U1") (pin "P$U24") (pinfunction "P1.04_P$U24") (pintype "bidirectional"))
    )
    (net (code "93") (name "P1.05") (class "Default")
      (node (ref "U1") (pin "P$T23") (pinfunction "P1.05_P$T23") (pintype "bidirectional"))
    )
    (net (code "94") (name "P1.06") (class "Default")
      (node (ref "U1") (pin "P$R24") (pinfunction "P1.06_P$R24") (pintype "bidirectional"))
    )
    (net (code "95") (name "P1.07") (class "Default")
      (node (ref "U1") (pin "P$P23") (pinfunction "P1.07_P$P23") (pintype "bidirectional"))
    )
    (net (code "96") (name "P1.09") (class "Default")
      (node (ref "U1") (pin "P$R1") (pinfunction "P1.09_P$R1") (pintype "bidirectional"))
    )
    (net (code "97") (name "P1.10") (class "Default")
      (node (ref "U1") (pin "P$A20") (pinfunction "P1.10_P$A20") (pintype "bidirectional"))
    )
    (net (code "98") (name "P1.11") (class "Default")
      (node (ref "U1") (pin "P$B19") (pinfunction "P1.11_P$B19") (pintype "bidirectional"))
    )
    (net (code "99") (name "P1.12") (class "Default")
      (node (ref "U1") (pin "P$B17") (pinfunction "P1.12_P$B17") (pintype "bidirectional"))
    )
    (net (code "100") (name "P1.13") (class "Default")
      (node (ref "U1") (pin "P$A16") (pinfunction "P1.13_P$A16") (pintype "bidirectional"))
    )
    (net (code "101") (name "P1.14") (class "Default")
      (node (ref "U1") (pin "P$B15") (pinfunction "P1.14_P$B15") (pintype "bidirectional"))
    )
    (net (code "102") (name "P1.15") (class "Default")
      (node (ref "U1") (pin "P$A14") (pinfunction "P1.15_P$A14") (pintype "bidirectional"))
    )
    (net (code "103") (name "PMIC_INT") (class "Default")
      (node (ref "IC1") (pin "A1") (pinfunction "~{INT}_A1") (pintype "bidirectional"))
      (node (ref "U1") (pin "P$T2") (pinfunction "P0.11_P$T2") (pintype "bidirectional"))
    )
    (net (code "104") (name "PREVGH") (class "Default")
      (node (ref "D5") (pin "1") (pinfunction "K_1") (pintype "bidirectional"))
      (node (ref "EPD_C9") (pin "2") (pinfunction "2_2") (pintype "passive"))
      (node (ref "J1") (pin "21") (pinfunction "21_21") (pintype "bidirectional"))
    )
    (net (code "105") (name "PREVGL") (class "Default")
      (node (ref "D2") (pin "2") (pinfunction "A_2") (pintype "bidirectional"))
      (node (ref "EPD_C11") (pin "2") (pinfunction "2_2") (pintype "passive"))
      (node (ref "J1") (pin "23") (pinfunction "23_23") (pintype "bidirectional"))
    )
    (net (code "106") (name "RESE") (class "Default")
      (node (ref "J1") (pin "3") (pinfunction "3_3") (pintype "bidirectional"))
      (node (ref "Q3") (pin "2") (pinfunction "S_2") (pintype "bidirectional"))
      (node (ref "R1_EP_DR") (pin "2") (pinfunction "2_2") (pintype "bidirectional"))
    )
    (net (code "107") (name "RESET") (class "Default")
      (node (ref "J2") (pin "6") (pinfunction "6_6") (pintype "bidirectional"))
      (node (ref "TP_RESET") (pin "TP") (pinfunction "TP_TP") (pintype "input"))
      (node (ref "U1") (pin "P$AC13") (pinfunction "P0.18/RESET_P$AC13") (pintype "bidirectional"))
    )
    (net (code "108") (name "SCK{slash}1.5B") (class "Default")
      (node (ref "J1") (pin "13") (pinfunction "13_13") (pintype "bidirectional"))
    )
    (net (code "109") (name "SCK{slash}2.2D") (class "Default")
      (node (ref "U1") (pin "P$A12") (pinfunction "P0.02/AIN0_P$A12") (pintype "bidirectional"))
    )
    (net (code "110") (name "SCL{slash}1.4C") (class "Default")
      (node (ref "IC2") (pin "C1") (pinfunction "SCL_C1") (pintype "bidirectional"))
      (node (ref "U3") (pin "7") (pinfunction "SCL_7") (pintype "input"))
    )
    (net (code "111") (name "SCL{slash}2.4C") (class "Default")
      (node (ref "IC1") (pin "B1") (pinfunction "SCL_B1") (pintype "bidirectional"))
      (node (ref "IC3") (pin "12") (pinfunction "SCX_12") (pintype "bidirectional"))
      (node (ref "R17") (pin "2") (pinfunction "2_2") (pintype "bidirectional"))
      (node (ref "R4") (pin "1") (pinfunction "1_1") (pintype "bidirectional"))
      (node (ref "TP_SCL") (pin "TP") (pinfunction "TP_TP") (pintype "input"))
      (node (ref "U1") (pin "P$M2") (pinfunction "P0.07_P$M2") (pintype "bidirectional"))
    )
    (net (code "112") (name "SDA{slash}1.4C") (class "Default")
      (node (ref "IC2") (pin "B2") (pinfunction "SDA_B2") (pintype "bidirectional"))
      (node (ref "U3") (pin "8") (pinfunction "SDA_8") (pintype "bidirectional"))
    )
    (net (code "113") (name "SDA{slash}2.4C") (class "Default")
      (node (ref "IC1") (pin "C1") (pinfunction "SDA_C1") (pintype "bidirectional"))
      (node (ref "IC3") (pin "2") (pinfunction "SDX_2") (pintype "bidirectional"))
      (node (ref "R18") (pin "2") (pinfunction "2_2") (pintype "bidirectional"))
      (node (ref "R2") (pin "1") (pinfunction "1_1") (pintype "bidirectional"))
      (node (ref "TP_SDA") (pin "TP") (pinfunction "TP_TP") (pintype "input"))
      (node (ref "U1") (pin "P$L1") (pinfunction "P0.06_P$L1") (pintype "bidirectional"))
    )
    (net (code "114") (name "SWDCLK") (class "Default")
      (node (ref "J2") (pin "4") (pinfunction "4_4") (pintype "bidirectional"))
      (node (ref "TP_SWDCLK") (pin "TP") (pinfunction "TP_TP") (pintype "input"))
      (node (ref "U1") (pin "P$AA24") (pinfunction "SWDCLK_P$AA24") (pintype "input"))
    )
    (net (code "115") (name "SWDIO") (class "Default")
      (node (ref "J2") (pin "2") (pinfunction "2_2") (pintype "bidirectional"))
      (node (ref "TP_SWDIO") (pin "TP") (pinfunction "TP_TP") (pintype "input"))
      (node (ref "U1") (pin "P$AC24") (pinfunction "SWDIO_P$AC24") (pintype "bidirectional"))
    )
    (net (code "116") (name "SWO") (class "Default")
      (node (ref "TP_SWO") (pin "TP") (pinfunction "TP_TP") (pintype "input"))
      (node (ref "U1") (pin "P$AD22") (pinfunction "P1.00_P$AD22") (pintype "bidirectional"))
    )
    (net (code "117") (name "VBAT{slash}1.2A") (class "Default")
      (node (ref "C27") (pin "2") (pinfunction "2_2") (pintype "passive"))
      (node (ref "TP_VBAT") (pin "TP") (pinfunction "TP_TP") (pintype "input"))
      (node (ref "U3") (pin "2") (pinfunction "CELL_2") (pintype "power_in"))
      (node (ref "U3") (pin "3") (pinfunction "VDD_3") (pintype "power_in"))
    )
    (net (code "118") (name "VBAT{slash}2.5C") (class "Default")
      (node (ref "C37") (pin "2") (pinfunction "2_2") (pintype "passive"))
      (node (ref "IC1") (pin "C2") (pinfunction "BAT_C2") (pintype "bidirectional"))
    )
    (net (code "119") (name "VBUS{slash}1.5D") (class "Default")
      (node (ref "C42") (pin "1") (pinfunction "1_1") (pintype "passive"))
      (node (ref "C43") (pin "1") (pinfunction "1_1") (pintype "passive"))
      (node (ref "D3") (pin "5") (pinfunction "VBUS_5") (pintype "bidirectional"))
      (node (ref "J4") (pin "A4_B9") (pinfunction "VBUS_A4_B9") (pintype "power_in"))
      (node (ref "J4") (pin "A9_B4") (pinfunction "VBUS_A9_B4") (pintype "power_in"))
    )
    (net (code "120") (name "VBUS{slash}2.6D") (class "Default")
      (node (ref "C21") (pin "1") (pinfunction "1_1") (pintype "passive"))
      (node (ref "C38") (pin "2") (pinfunction "2_2") (pintype "passive"))
      (node (ref "IC1") (pin "A2") (pinfunction "IN_A2") (pintype "bidirectional"))
      (node (ref "U1") (pin "P$AD2") (pinfunction "VBUS_P$AD2") (pintype "power_in"))
    )
    (net (code "121") (name "VREG") (class "Default")
      (node (ref "C23") (pin "1") (pinfunction "1_1") (pintype "passive"))
      (node (ref "C24") (pin "2") (pinfunction "2_2") (pintype "passive"))
      (node (ref "C39") (pin "1") (pinfunction "1_1") (pintype "passive"))
      (node (ref "IC1") (pin "B2") (pinfunction "SYS_B2") (pintype "bidirectional"))
      (node (ref "IC9") (pin "A1") (pinfunction "EN_A1") (pintype "bidirectional"))
      (node (ref "IC9") (pin "A2") (pinfunction "VIN_1_A2") (pintype "bidirectional"))
      (node (ref "IC9") (pin "A3") (pinfunction "VIN_2_A3") (pintype "bidirectional"))
      (node (ref "TP_VREG") (pin "TP") (pinfunction "TP_TP") (pintype "input"))
    )
    (net (code "122") (name "unconnected-(ANT1-NC-Pad2)") (class "Default")
      (node (ref "ANT1") (pin "2") (pinfunction "NC_2") (pintype "no_connect"))
    )
    (net (code "123") (name "unconnected-(C27-Pad1)") (class "Default")
      (node (ref "C27") (pin "1") (pinfunction "1_1") (pintype "passive"))
    )
    (net (code "124") (name "unconnected-(EPD_C1-Pad1)") (class "Default")
      (node (ref "EPD_C1") (pin "1") (pinfunction "1_1") (pintype "passive"))
    )
    (net (code "125") (name "unconnected-(EPD_C2-Pad1)") (class "Default")
      (node (ref "EPD_C2") (pin "1") (pinfunction "1_1") (pintype "passive"))
    )
    (net (code "126") (name "unconnected-(IC3-ASCL-Pad11)") (class "Default")
      (node (ref "IC3") (pin "11") (pinfunction "ASCL_11") (pintype "bidirectional"))
    )
    (net (code "127") (name "unconnected-(IC3-ASDA-Pad4)") (class "Default")
      (node (ref "IC3") (pin "4") (pinfunction "ASDA_4") (pintype "bidirectional"))
    )
    (net (code "128") (name "unconnected-(J1-Pad1)") (class "Default")
      (node (ref "J1") (pin "1") (pinfunction "1_1") (pintype "bidirectional"))
    )
    (net (code "129") (name "unconnected-(J1-Pad6)") (class "Default")
      (node (ref "J1") (pin "6") (pinfunction "6_6") (pintype "bidirectional"))
    )
    (net (code "130") (name "unconnected-(J1-Pad7)") (class "Default")
      (node (ref "J1") (pin "7") (pinfunction "7_7") (pintype "bidirectional"))
    )
    (net (code "131") (name "unconnected-(J1-PadMP2)") (class "Default")
      (node (ref "J1") (pin "MP2") (pinfunction "MP2_MP2") (pintype "bidirectional"))
    )
    (net (code "132") (name "unconnected-(J4-SBU1-PadA8)") (class "Default")
      (node (ref "J4") (pin "A8") (pinfunction "SBU1_A8") (pintype "bidirectional"))
    )
    (net (code "133") (name "unconnected-(J4-SBU2-PadB8)") (class "Default")
      (node (ref "J4") (pin "B8") (pinfunction "SBU2_B8") (pintype "bidirectional"))
    )
    (net (code "134") (name "unconnected-(U1-DCCH-PadP$AB2)") (class "Default")
      (node (ref "U1") (pin "P$AB2") (pinfunction "DCCH_P$AB2") (pintype "bidirectional"))
    )
  )
)
